# LEDMotherboardv2.net
KiCad netlist of a schematic drawn in EAGLE
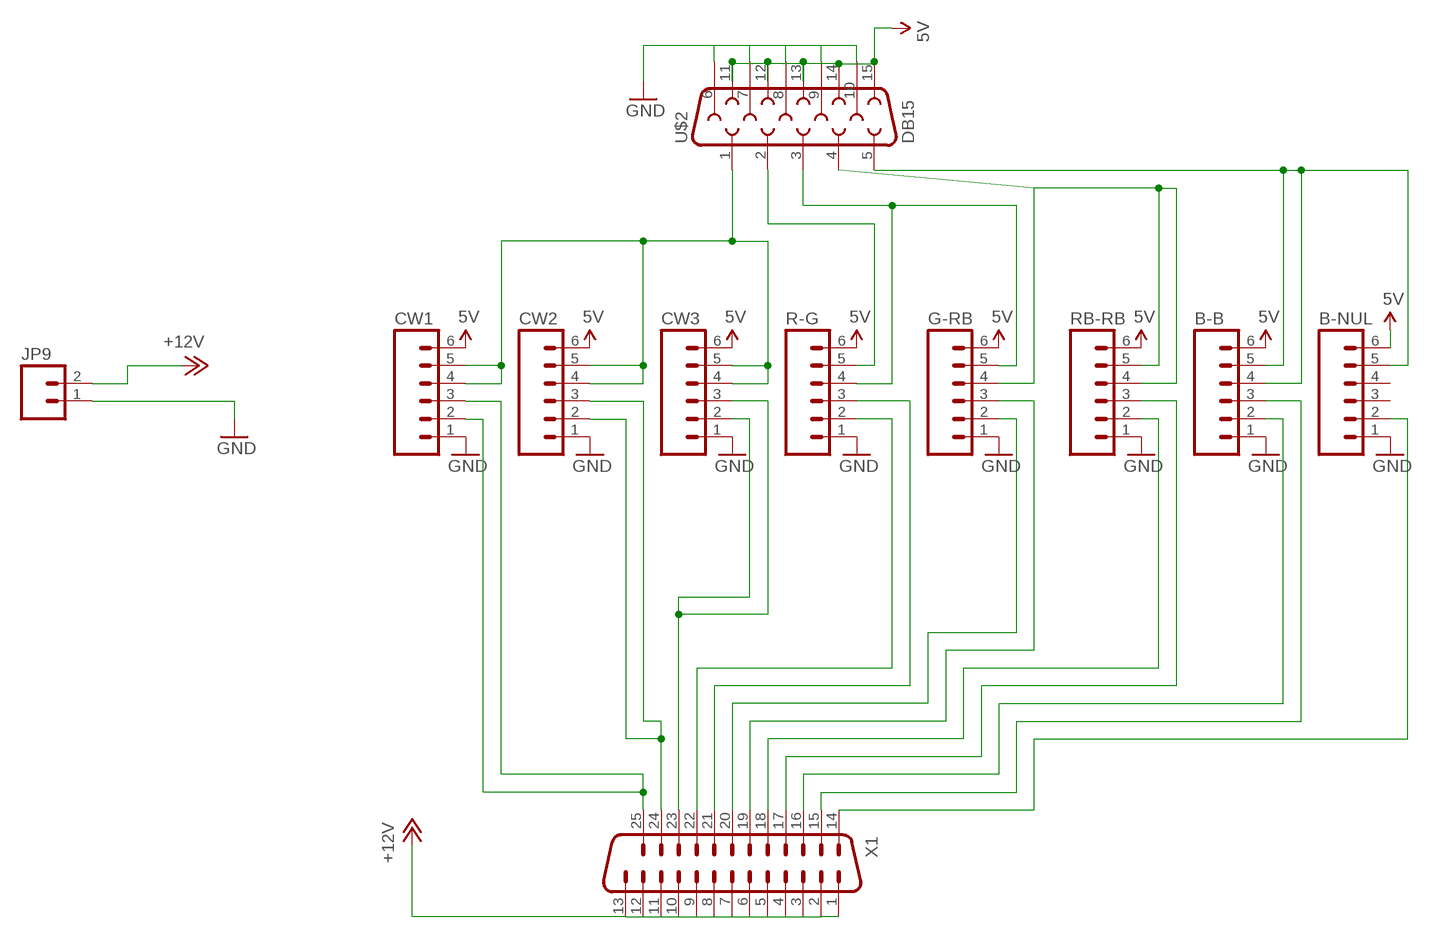
[diagram p0: schematic, sheet 1]

(export (version "E")
  (design (tool "Eeschema 10.0.6"))
  (components
    (comp (ref "B-B")
      (value "M06LOCK_LONGPADS")
      (footprint "eagle-import:1X06_LOCK_LONGPADS")
      (libsource (lib "eagle-import") (part "M06LOCK_LONGPADS"))
    )
    (comp (ref "B-NUL")
      (value "M06LOCK_LONGPADS")
      (footprint "eagle-import:1X06_LOCK_LONGPADS")
      (libsource (lib "eagle-import") (part "M06LOCK_LONGPADS"))
    )
    (comp (ref "CW1")
      (value "M06LOCK_LONGPADS")
      (footprint "eagle-import:1X06_LOCK_LONGPADS")
      (libsource (lib "eagle-import") (part "M06LOCK_LONGPADS"))
    )
    (comp (ref "CW2")
      (value "M06LOCK_LONGPADS")
      (footprint "eagle-import:1X06_LOCK_LONGPADS")
      (libsource (lib "eagle-import") (part "M06LOCK_LONGPADS"))
    )
    (comp (ref "CW3")
      (value "M06LOCK_LONGPADS")
      (footprint "eagle-import:1X06_LOCK_LONGPADS")
      (libsource (lib "eagle-import") (part "M06LOCK_LONGPADS"))
    )
    (comp (ref "G-RB")
      (value "M06LOCK_LONGPADS")
      (footprint "eagle-import:1X06_LOCK_LONGPADS")
      (libsource (lib "eagle-import") (part "M06LOCK_LONGPADS"))
    )
    (comp (ref "JP9")
      (value "M02")
      (footprint "eagle-import:02P")
      (libsource (lib "eagle-import") (part "M02"))
    )
    (comp (ref "R-G")
      (value "M06LOCK_LONGPADS")
      (footprint "eagle-import:1X06_LOCK_LONGPADS")
      (libsource (lib "eagle-import") (part "M06LOCK_LONGPADS"))
    )
    (comp (ref "RB-RB")
      (value "M06LOCK_LONGPADS")
      (footprint "eagle-import:1X06_LOCK_LONGPADS")
      (libsource (lib "eagle-import") (part "M06LOCK_LONGPADS"))
    )
    (comp (ref "U$2")
      (value "DB15")
      (footprint "eagle-import:DB15")
      (libsource (lib "eagle-import") (part "DB15"))
    )
    (comp (ref "X1")
      (value "DB25HP")
      (footprint "eagle-import:M25HP")
      (libsource (lib "eagle-import") (part "DB25HP"))
    )
  )
  (nets
    (net (code "1") (name "+12V") (class "Default")
      (node (ref "JP9") (pin "2") (pinfunction "2_2") (pintype "passive"))
      (node (ref "X1") (pin "1") (pinfunction "1_1") (pintype "passive"))
      (node (ref "X1") (pin "10") (pinfunction "10_10") (pintype "passive"))
      (node (ref "X1") (pin "11") (pinfunction "11_11") (pintype "passive"))
      (node (ref "X1") (pin "12") (pinfunction "12_12") (pintype "passive"))
      (node (ref "X1") (pin "13") (pinfunction "13_13") (pintype "passive"))
      (node (ref "X1") (pin "2") (pinfunction "2_2") (pintype "passive"))
      (node (ref "X1") (pin "3") (pinfunction "3_3") (pintype "passive"))
      (node (ref "X1") (pin "4") (pinfunction "4_4") (pintype "passive"))
      (node (ref "X1") (pin "5") (pinfunction "5_5") (pintype "passive"))
      (node (ref "X1") (pin "6") (pinfunction "6_6") (pintype "passive"))
      (node (ref "X1") (pin "7") (pinfunction "7_7") (pintype "passive"))
      (node (ref "X1") (pin "8") (pinfunction "8_8") (pintype "passive"))
      (node (ref "X1") (pin "9") (pinfunction "9_9") (pintype "passive"))
    )
    (net (code "2") (name "5V") (class "Default")
      (node (ref "B-B") (pin "6") (pinfunction "6_6") (pintype "passive"))
      (node (ref "B-NUL") (pin "6") (pinfunction "6_6") (pintype "passive"))
      (node (ref "CW1") (pin "6") (pinfunction "6_6") (pintype "passive"))
      (node (ref "CW2") (pin "6") (pinfunction "6_6") (pintype "passive"))
      (node (ref "CW3") (pin "6") (pinfunction "6_6") (pintype "passive"))
      (node (ref "G-RB") (pin "6") (pinfunction "6_6") (pintype "passive"))
      (node (ref "R-G") (pin "6") (pinfunction "6_6") (pintype "passive"))
      (node (ref "RB-RB") (pin "6") (pinfunction "6_6") (pintype "passive"))
      (node (ref "U$2") (pin "11") (pinfunction "11_11") (pintype "passive"))
      (node (ref "U$2") (pin "12") (pinfunction "12_12") (pintype "passive"))
      (node (ref "U$2") (pin "13") (pinfunction "13_13") (pintype "passive"))
      (node (ref "U$2") (pin "14") (pinfunction "14_14") (pintype "passive"))
      (node (ref "U$2") (pin "15") (pinfunction "15_15") (pintype "passive"))
    )
    (net (code "3") (name "GND") (class "Default")
      (node (ref "B-B") (pin "1") (pinfunction "1_1") (pintype "passive"))
      (node (ref "B-NUL") (pin "1") (pinfunction "1_1") (pintype "passive"))
      (node (ref "CW1") (pin "1") (pinfunction "1_1") (pintype "passive"))
      (node (ref "CW2") (pin "1") (pinfunction "1_1") (pintype "passive"))
      (node (ref "CW3") (pin "1") (pinfunction "1_1") (pintype "passive"))
      (node (ref "G-RB") (pin "1") (pinfunction "1_1") (pintype "passive"))
      (node (ref "JP9") (pin "1") (pinfunction "1_1") (pintype "passive"))
      (node (ref "R-G") (pin "1") (pinfunction "1_1") (pintype "passive"))
      (node (ref "RB-RB") (pin "1") (pinfunction "1_1") (pintype "passive"))
      (node (ref "U$2") (pin "10") (pinfunction "10_10") (pintype "passive"))
      (node (ref "U$2") (pin "6") (pinfunction "6_6") (pintype "passive"))
      (node (ref "U$2") (pin "7") (pinfunction "7_7") (pintype "passive"))
      (node (ref "U$2") (pin "8") (pinfunction "8_8") (pintype "passive"))
      (node (ref "U$2") (pin "9") (pinfunction "9_9") (pintype "passive"))
    )
    (net (code "4") (name "Net-(B-B-Pad2)") (class "Default")
      (node (ref "B-B") (pin "2") (pinfunction "2_2") (pintype "passive"))
      (node (ref "X1") (pin "16") (pinfunction "16_16") (pintype "passive"))
    )
    (net (code "5") (name "Net-(B-B-Pad3)") (class "Default")
      (node (ref "B-B") (pin "3") (pinfunction "3_3") (pintype "passive"))
      (node (ref "X1") (pin "15") (pinfunction "15_15") (pintype "passive"))
    )
    (net (code "6") (name "Net-(B-B-Pad4)") (class "Default")
      (node (ref "B-B") (pin "4") (pinfunction "4_4") (pintype "passive"))
      (node (ref "B-B") (pin "5") (pinfunction "5_5") (pintype "passive"))
      (node (ref "B-NUL") (pin "5") (pinfunction "5_5") (pintype "passive"))
      (node (ref "U$2") (pin "5") (pinfunction "5_5") (pintype "passive"))
    )
    (net (code "7") (name "Net-(B-NUL-Pad2)") (class "Default")
      (node (ref "B-NUL") (pin "2") (pinfunction "2_2") (pintype "passive"))
      (node (ref "X1") (pin "14") (pinfunction "14_14") (pintype "passive"))
    )
    (net (code "8") (name "Net-(CW1-Pad2)") (class "Default")
      (node (ref "CW1") (pin "2") (pinfunction "2_2") (pintype "passive"))
      (node (ref "CW1") (pin "3") (pinfunction "3_3") (pintype "passive"))
      (node (ref "X1") (pin "25") (pinfunction "25_25") (pintype "passive"))
    )
    (net (code "9") (name "Net-(CW1-Pad4)") (class "Default")
      (node (ref "CW1") (pin "4") (pinfunction "4_4") (pintype "passive"))
      (node (ref "CW1") (pin "5") (pinfunction "5_5") (pintype "passive"))
      (node (ref "CW2") (pin "4") (pinfunction "4_4") (pintype "passive"))
      (node (ref "CW2") (pin "5") (pinfunction "5_5") (pintype "passive"))
      (node (ref "CW3") (pin "4") (pinfunction "4_4") (pintype "passive"))
      (node (ref "CW3") (pin "5") (pinfunction "5_5") (pintype "passive"))
      (node (ref "U$2") (pin "1") (pinfunction "1_1") (pintype "passive"))
    )
    (net (code "10") (name "Net-(CW2-Pad2)") (class "Default")
      (node (ref "CW2") (pin "2") (pinfunction "2_2") (pintype "passive"))
      (node (ref "CW2") (pin "3") (pinfunction "3_3") (pintype "passive"))
      (node (ref "X1") (pin "24") (pinfunction "24_24") (pintype "passive"))
    )
    (net (code "11") (name "Net-(CW3-Pad2)") (class "Default")
      (node (ref "CW3") (pin "2") (pinfunction "2_2") (pintype "passive"))
      (node (ref "CW3") (pin "3") (pinfunction "3_3") (pintype "passive"))
      (node (ref "X1") (pin "23") (pinfunction "23_23") (pintype "passive"))
    )
    (net (code "12") (name "Net-(G-RB-Pad2)") (class "Default")
      (node (ref "G-RB") (pin "2") (pinfunction "2_2") (pintype "passive"))
      (node (ref "X1") (pin "20") (pinfunction "20_20") (pintype "passive"))
    )
    (net (code "13") (name "Net-(G-RB-Pad3)") (class "Default")
      (node (ref "G-RB") (pin "3") (pinfunction "3_3") (pintype "passive"))
      (node (ref "X1") (pin "19") (pinfunction "19_19") (pintype "passive"))
    )
    (net (code "14") (name "Net-(G-RB-Pad4)") (class "Default")
      (node (ref "G-RB") (pin "4") (pinfunction "4_4") (pintype "passive"))
      (node (ref "RB-RB") (pin "4") (pinfunction "4_4") (pintype "passive"))
      (node (ref "RB-RB") (pin "5") (pinfunction "5_5") (pintype "passive"))
      (node (ref "U$2") (pin "4") (pinfunction "4_4") (pintype "passive"))
    )
    (net (code "15") (name "Net-(G-RB-Pad5)") (class "Default")
      (node (ref "G-RB") (pin "5") (pinfunction "5_5") (pintype "passive"))
      (node (ref "R-G") (pin "4") (pinfunction "4_4") (pintype "passive"))
      (node (ref "U$2") (pin "3") (pinfunction "3_3") (pintype "passive"))
    )
    (net (code "16") (name "Net-(R-G-Pad2)") (class "Default")
      (node (ref "R-G") (pin "2") (pinfunction "2_2") (pintype "passive"))
      (node (ref "X1") (pin "22") (pinfunction "22_22") (pintype "passive"))
    )
    (net (code "17") (name "Net-(R-G-Pad3)") (class "Default")
      (node (ref "R-G") (pin "3") (pinfunction "3_3") (pintype "passive"))
      (node (ref "X1") (pin "21") (pinfunction "21_21") (pintype "passive"))
    )
    (net (code "18") (name "Net-(R-G-Pad5)") (class "Default")
      (node (ref "R-G") (pin "5") (pinfunction "5_5") (pintype "passive"))
      (node (ref "U$2") (pin "2") (pinfunction "2_2") (pintype "passive"))
    )
    (net (code "19") (name "Net-(RB-RB-Pad2)") (class "Default")
      (node (ref "RB-RB") (pin "2") (pinfunction "2_2") (pintype "passive"))
      (node (ref "X1") (pin "18") (pinfunction "18_18") (pintype "passive"))
    )
    (net (code "20") (name "Net-(RB-RB-Pad3)") (class "Default")
      (node (ref "RB-RB") (pin "3") (pinfunction "3_3") (pintype "passive"))
      (node (ref "X1") (pin "17") (pinfunction "17_17") (pintype "passive"))
    )
    (net (code "21") (name "unconnected-(B-NUL-Pad3)") (class "Default")
      (node (ref "B-NUL") (pin "3") (pinfunction "3_3") (pintype "passive"))
    )
    (net (code "22") (name "unconnected-(B-NUL-Pad4)") (class "Default")
      (node (ref "B-NUL") (pin "4") (pinfunction "4_4") (pintype "passive"))
    )
  )
)
